# flex.net
KiCad netlist of a schematic drawn in EAGLE
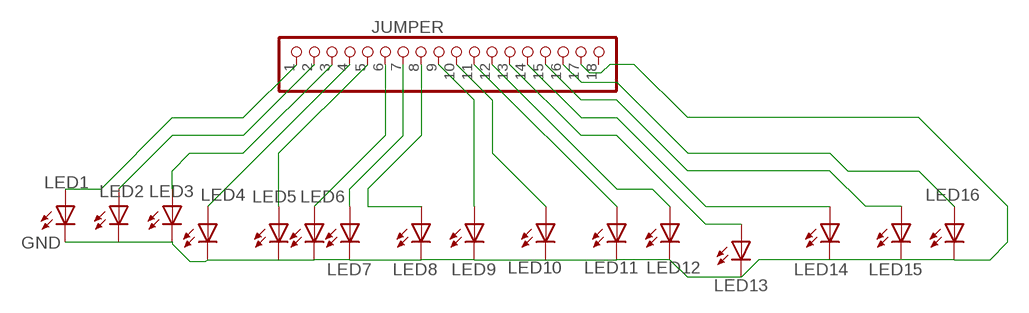
[diagram p0: schematic, sheet 1]

(export (version "E")
  (design (tool "Eeschema 10.0.6"))
  (components
    (comp (ref "JUMPER")
      (value "PINHD-1X18")
      (footprint "eagle-import:1X18")
      (libsource (lib "eagle-import") (part "PINHD-1X18"))
    )
    (comp (ref "LED1")
      (value "LED5MM")
      (footprint "eagle-import:LED5MM")
      (libsource (lib "eagle-import") (part "LED5MM"))
    )
    (comp (ref "LED2")
      (value "LED5MM")
      (footprint "eagle-import:LED5MM")
      (libsource (lib "eagle-import") (part "LED5MM"))
    )
    (comp (ref "LED3")
      (value "LED5MM")
      (footprint "eagle-import:LED5MM")
      (libsource (lib "eagle-import") (part "LED5MM"))
    )
    (comp (ref "LED4")
      (value "LED5MM")
      (footprint "eagle-import:LED5MM")
      (libsource (lib "eagle-import") (part "LED5MM"))
    )
    (comp (ref "LED5")
      (value "LED5MM")
      (footprint "eagle-import:LED5MM")
      (libsource (lib "eagle-import") (part "LED5MM"))
    )
    (comp (ref "LED6")
      (value "LED5MM")
      (footprint "eagle-import:LED5MM")
      (libsource (lib "eagle-import") (part "LED5MM"))
    )
    (comp (ref "LED7")
      (value "LED5MM")
      (footprint "eagle-import:LED5MM")
      (libsource (lib "eagle-import") (part "LED5MM"))
    )
    (comp (ref "LED8")
      (value "LED5MM")
      (footprint "eagle-import:LED5MM")
      (libsource (lib "eagle-import") (part "LED5MM"))
    )
    (comp (ref "LED9")
      (value "LED5MM")
      (footprint "eagle-import:LED5MM")
      (libsource (lib "eagle-import") (part "LED5MM"))
    )
    (comp (ref "LED10")
      (value "LED5MM")
      (footprint "eagle-import:LED5MM")
      (libsource (lib "eagle-import") (part "LED5MM"))
    )
    (comp (ref "LED11")
      (value "LED5MM")
      (footprint "eagle-import:LED5MM")
      (libsource (lib "eagle-import") (part "LED5MM"))
    )
    (comp (ref "LED12")
      (value "LED5MM")
      (footprint "eagle-import:LED5MM")
      (libsource (lib "eagle-import") (part "LED5MM"))
    )
    (comp (ref "LED13")
      (value "LED5MM")
      (footprint "eagle-import:LED5MM")
      (libsource (lib "eagle-import") (part "LED5MM"))
    )
    (comp (ref "LED14")
      (value "LED5MM")
      (footprint "eagle-import:LED5MM")
      (libsource (lib "eagle-import") (part "LED5MM"))
    )
    (comp (ref "LED15")
      (value "LED5MM")
      (footprint "eagle-import:LED5MM")
      (libsource (lib "eagle-import") (part "LED5MM"))
    )
    (comp (ref "LED16")
      (value "LED5MM")
      (footprint "eagle-import:LED5MM")
      (libsource (lib "eagle-import") (part "LED5MM"))
    )
  )
  (nets
    (net (code "1") (name "/GND") (class "Default")
      (node (ref "JUMPER") (pin "17") (pinfunction "17_17") (pintype "passive"))
      (node (ref "LED1") (pin "K") (pinfunction "C_K") (pintype "passive"))
      (node (ref "LED10") (pin "K") (pinfunction "C_K") (pintype "passive"))
      (node (ref "LED11") (pin "K") (pinfunction "C_K") (pintype "passive"))
      (node (ref "LED12") (pin "K") (pinfunction "C_K") (pintype "passive"))
      (node (ref "LED13") (pin "K") (pinfunction "C_K") (pintype "passive"))
      (node (ref "LED14") (pin "K") (pinfunction "C_K") (pintype "passive"))
      (node (ref "LED15") (pin "K") (pinfunction "C_K") (pintype "passive"))
      (node (ref "LED16") (pin "K") (pinfunction "C_K") (pintype "passive"))
      (node (ref "LED2") (pin "K") (pinfunction "C_K") (pintype "passive"))
      (node (ref "LED3") (pin "K") (pinfunction "C_K") (pintype "passive"))
      (node (ref "LED4") (pin "K") (pinfunction "C_K") (pintype "passive"))
      (node (ref "LED5") (pin "K") (pinfunction "C_K") (pintype "passive"))
      (node (ref "LED6") (pin "K") (pinfunction "C_K") (pintype "passive"))
      (node (ref "LED7") (pin "K") (pinfunction "C_K") (pintype "passive"))
      (node (ref "LED8") (pin "K") (pinfunction "C_K") (pintype "passive"))
      (node (ref "LED9") (pin "K") (pinfunction "C_K") (pintype "passive"))
    )
    (net (code "2") (name "Net-(JUMPER-Pad1)") (class "Default")
      (node (ref "JUMPER") (pin "1") (pinfunction "1_1") (pintype "passive"))
      (node (ref "LED1") (pin "A") (pinfunction "A_A") (pintype "passive"))
    )
    (net (code "3") (name "Net-(JUMPER-Pad2)") (class "Default")
      (node (ref "JUMPER") (pin "2") (pinfunction "2_2") (pintype "passive"))
      (node (ref "LED2") (pin "A") (pinfunction "A_A") (pintype "passive"))
    )
    (net (code "4") (name "Net-(JUMPER-Pad3)") (class "Default")
      (node (ref "JUMPER") (pin "3") (pinfunction "3_3") (pintype "passive"))
      (node (ref "LED3") (pin "A") (pinfunction "A_A") (pintype "passive"))
    )
    (net (code "5") (name "Net-(JUMPER-Pad4)") (class "Default")
      (node (ref "JUMPER") (pin "4") (pinfunction "4_4") (pintype "passive"))
      (node (ref "LED4") (pin "A") (pinfunction "A_A") (pintype "passive"))
    )
    (net (code "6") (name "Net-(JUMPER-Pad5)") (class "Default")
      (node (ref "JUMPER") (pin "5") (pinfunction "5_5") (pintype "passive"))
      (node (ref "LED5") (pin "A") (pinfunction "A_A") (pintype "passive"))
    )
    (net (code "7") (name "Net-(JUMPER-Pad6)") (class "Default")
      (node (ref "JUMPER") (pin "6") (pinfunction "6_6") (pintype "passive"))
      (node (ref "LED6") (pin "A") (pinfunction "A_A") (pintype "passive"))
    )
    (net (code "8") (name "Net-(JUMPER-Pad7)") (class "Default")
      (node (ref "JUMPER") (pin "7") (pinfunction "7_7") (pintype "passive"))
      (node (ref "LED7") (pin "A") (pinfunction "A_A") (pintype "passive"))
    )
    (net (code "9") (name "Net-(JUMPER-Pad8)") (class "Default")
      (node (ref "JUMPER") (pin "8") (pinfunction "8_8") (pintype "passive"))
      (node (ref "LED8") (pin "A") (pinfunction "A_A") (pintype "passive"))
    )
    (net (code "10") (name "Net-(JUMPER-Pad9)") (class "Default")
      (node (ref "JUMPER") (pin "9") (pinfunction "9_9") (pintype "passive"))
      (node (ref "LED9") (pin "A") (pinfunction "A_A") (pintype "passive"))
    )
    (net (code "11") (name "Net-(JUMPER-Pad10)") (class "Default")
      (node (ref "JUMPER") (pin "10") (pinfunction "10_10") (pintype "passive"))
      (node (ref "LED10") (pin "A") (pinfunction "A_A") (pintype "passive"))
    )
    (net (code "12") (name "Net-(JUMPER-Pad11)") (class "Default")
      (node (ref "JUMPER") (pin "11") (pinfunction "11_11") (pintype "passive"))
      (node (ref "LED11") (pin "A") (pinfunction "A_A") (pintype "passive"))
    )
    (net (code "13") (name "Net-(JUMPER-Pad12)") (class "Default")
      (node (ref "JUMPER") (pin "12") (pinfunction "12_12") (pintype "passive"))
      (node (ref "LED12") (pin "A") (pinfunction "A_A") (pintype "passive"))
    )
    (net (code "14") (name "Net-(JUMPER-Pad13)") (class "Default")
      (node (ref "JUMPER") (pin "13") (pinfunction "13_13") (pintype "passive"))
      (node (ref "LED13") (pin "A") (pinfunction "A_A") (pintype "passive"))
    )
    (net (code "15") (name "Net-(JUMPER-Pad14)") (class "Default")
      (node (ref "JUMPER") (pin "14") (pinfunction "14_14") (pintype "passive"))
      (node (ref "LED14") (pin "A") (pinfunction "A_A") (pintype "passive"))
    )
    (net (code "16") (name "Net-(JUMPER-Pad15)") (class "Default")
      (node (ref "JUMPER") (pin "15") (pinfunction "15_15") (pintype "passive"))
      (node (ref "LED15") (pin "A") (pinfunction "A_A") (pintype "passive"))
    )
    (net (code "17") (name "Net-(JUMPER-Pad16)") (class "Default")
      (node (ref "JUMPER") (pin "16") (pinfunction "16_16") (pintype "passive"))
      (node (ref "LED16") (pin "A") (pinfunction "A_A") (pintype "passive"))
    )
    (net (code "18") (name "unconnected-(JUMPER-Pad18)") (class "Default")
      (node (ref "JUMPER") (pin "18") (pinfunction "18_18") (pintype "passive"))
    )
  )
)
